# SDCardv1.net
KiCad netlist of a schematic drawn in EAGLE
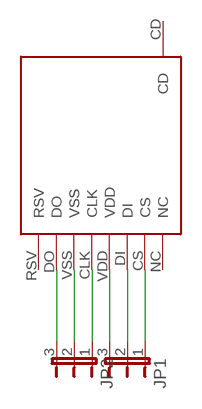
[diagram p0: schematic, sheet 1]

(export (version "E")
  (design (tool "Eeschema 10.0.6"))
  (components
    (comp (ref "JP1")
      (value "JP2W")
      (footprint "eagle-import:JP2W")
      (libsource (lib "eagle-import") (part "JP2W"))
    )
    (comp (ref "JP2")
      (value "JP2W")
      (footprint "eagle-import:JP2W")
      (libsource (lib "eagle-import") (part "JP2W"))
    )
    (comp (ref "U$1")
      (value "MICROSD_SOCKET")
      (footprint "eagle-import:MICROSD_SOCKET")
      (libsource (lib "eagle-import") (part "MICROSD_SOCKET"))
    )
  )
  (nets
    (net (code "1") (name "Net-(JP1-Pad1)") (class "Default")
      (node (ref "JP1") (pin "1") (pinfunction "1_1") (pintype "passive"))
      (node (ref "U$1") (pin "CS") (pinfunction "CS_CS") (pintype "bidirectional"))
    )
    (net (code "2") (name "Net-(JP1-Pad2)") (class "Default")
      (node (ref "JP1") (pin "2") (pinfunction "2_2") (pintype "passive"))
      (node (ref "U$1") (pin "DI") (pinfunction "DI_DI") (pintype "bidirectional"))
    )
    (net (code "3") (name "Net-(JP1-Pad3)") (class "Default")
      (node (ref "JP1") (pin "3") (pinfunction "3_3") (pintype "passive"))
      (node (ref "U$1") (pin "VDD") (pinfunction "VDD_VDD") (pintype "bidirectional"))
    )
    (net (code "4") (name "Net-(JP2-Pad1)") (class "Default")
      (node (ref "JP2") (pin "1") (pinfunction "1_1") (pintype "passive"))
      (node (ref "U$1") (pin "CLK") (pinfunction "CLK_CLK") (pintype "bidirectional"))
    )
    (net (code "5") (name "Net-(JP2-Pad2)") (class "Default")
      (node (ref "JP2") (pin "2") (pinfunction "2_2") (pintype "passive"))
      (node (ref "U$1") (pin "VSS") (pinfunction "VSS_VSS") (pintype "bidirectional"))
    )
    (net (code "6") (name "Net-(JP2-Pad3)") (class "Default")
      (node (ref "JP2") (pin "3") (pinfunction "3_3") (pintype "passive"))
      (node (ref "U$1") (pin "DO") (pinfunction "DO_DO") (pintype "bidirectional"))
    )
    (net (code "7") (name "unconnected-(U$1-PadCD)") (class "Default")
      (node (ref "U$1") (pin "CD") (pinfunction "CD_CD") (pintype "bidirectional"))
    )
    (net (code "8") (name "unconnected-(U$1-PadNC)") (class "Default")
      (node (ref "U$1") (pin "NC") (pinfunction "NC_NC") (pintype "bidirectional"))
    )
    (net (code "9") (name "unconnected-(U$1-PadRSV)") (class "Default")
      (node (ref "U$1") (pin "RSV") (pinfunction "RSV_RSV") (pintype "bidirectional"))
    )
  )
)
